# zx81a.net
KiCad netlist of a schematic drawn in EAGLE
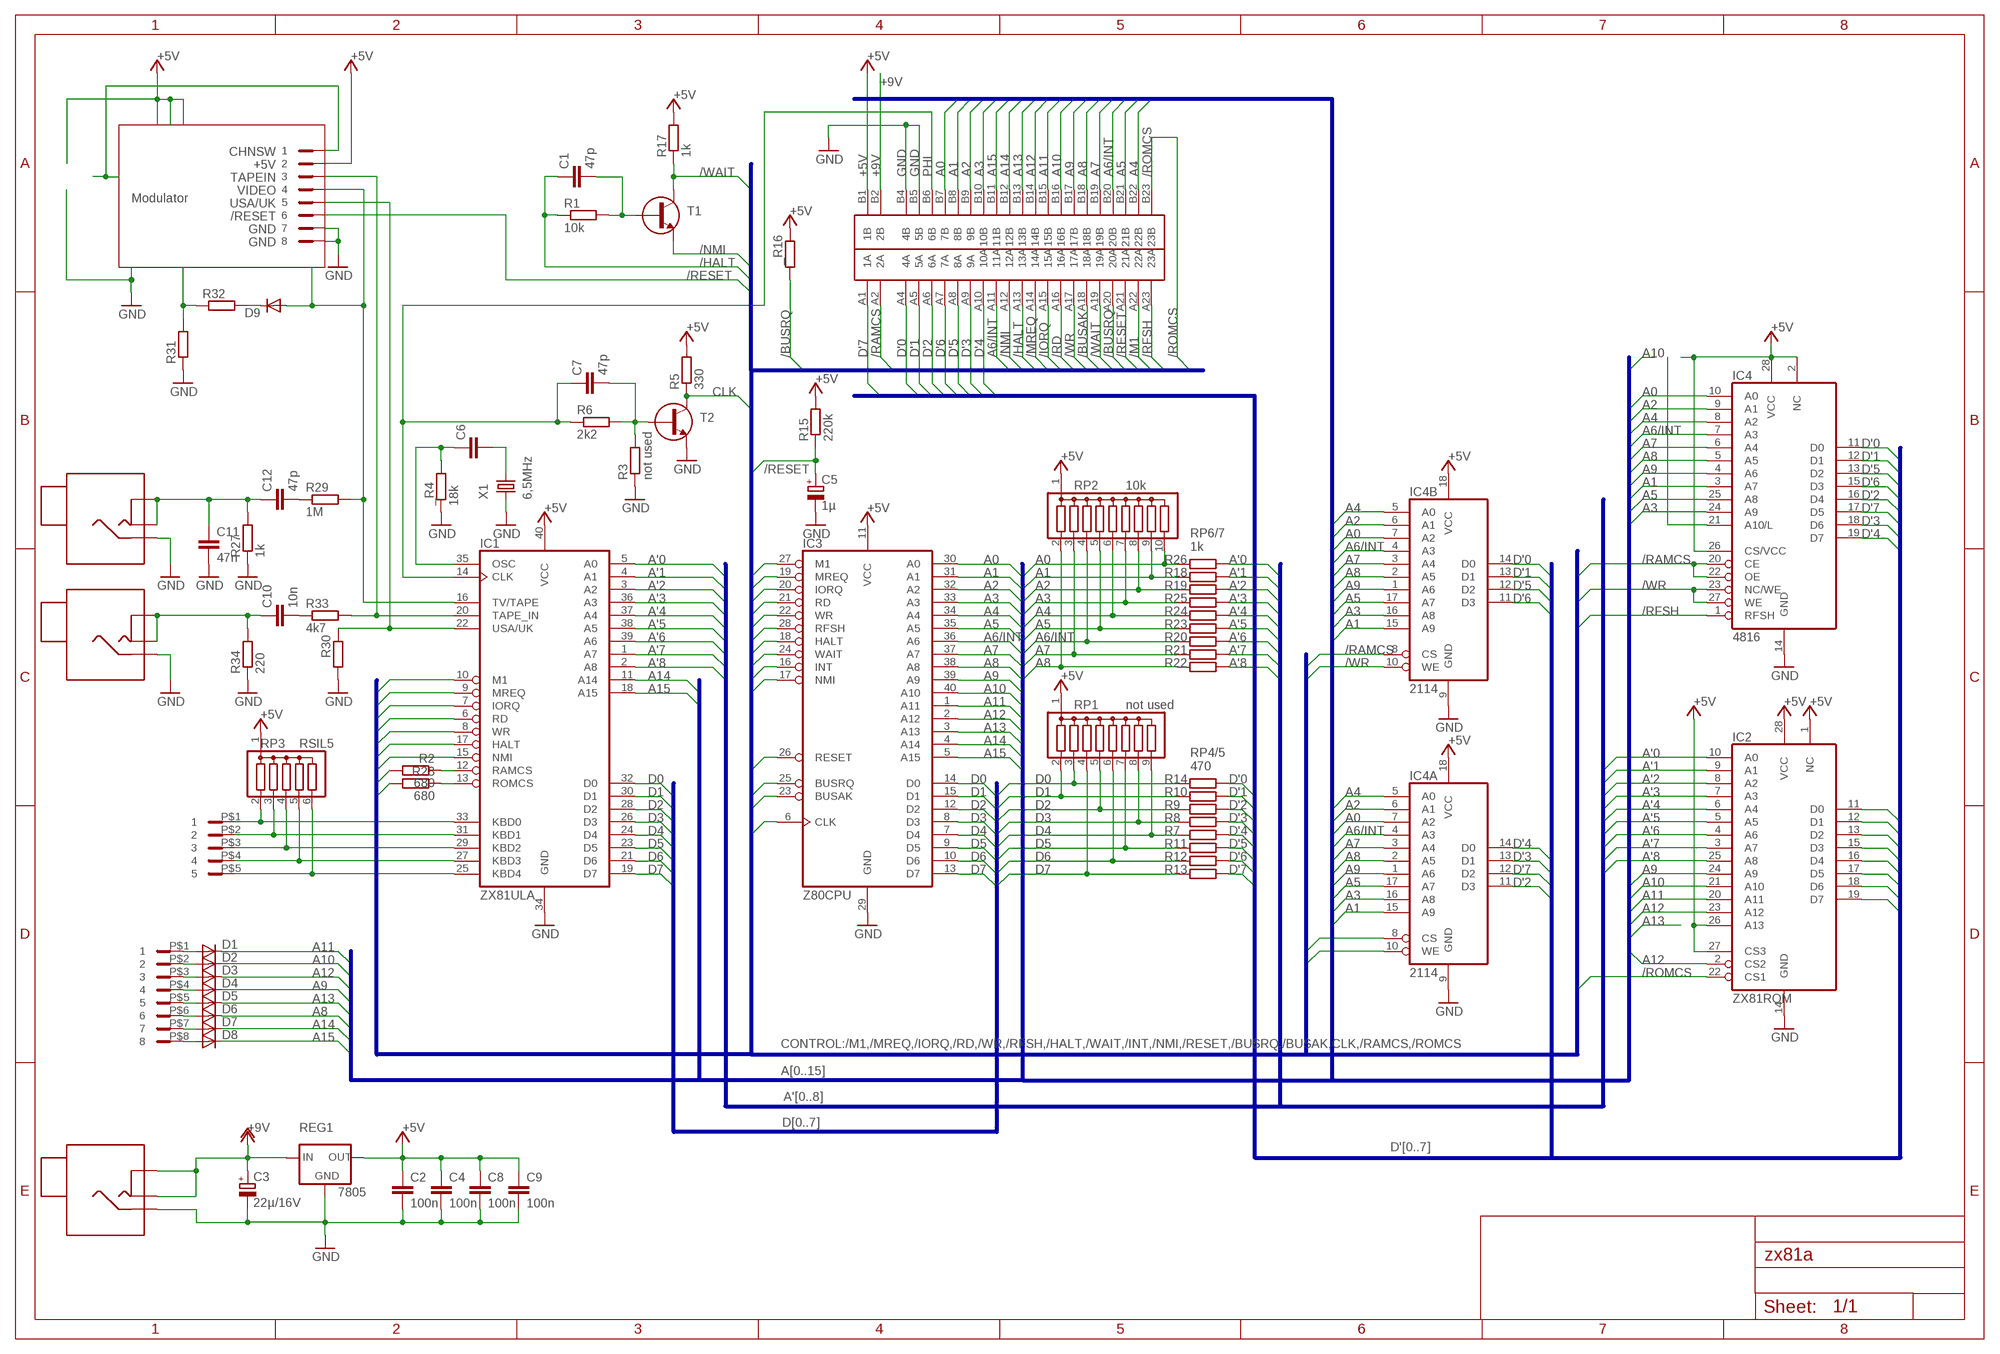
[diagram p0: schematic, sheet 1]

(export (version "E")
  (design (tool "Eeschema 10.0.6"))
  (components
    (comp (ref "C1")
      (value "47p")
      (footprint "eagle-import:C025-025X050")
      (libsource (lib "eagle-import") (part "C"))
    )
    (comp (ref "C2")
      (value "100n")
      (footprint "eagle-import:C025-025X050")
      (libsource (lib "eagle-import") (part "C"))
    )
    (comp (ref "C3")
      (value "22µ/16V")
      (footprint "eagle-import:E5-5")
      (libsource (lib "eagle-import") (part "CPOLE5-5"))
    )
    (comp (ref "C4")
      (value "100n")
      (footprint "eagle-import:C025-025X050")
      (libsource (lib "eagle-import") (part "C"))
    )
    (comp (ref "C5")
      (value "1µ")
      (footprint "eagle-import:E3,8-5")
      (libsource (lib "eagle-import") (part "CPOLE3,8-5"))
    )
    (comp (ref "C6")
      (value "C")
      (footprint "eagle-import:C025-025X050")
      (libsource (lib "eagle-import") (part "C"))
    )
    (comp (ref "C7")
      (value "47p")
      (footprint "eagle-import:C025-025X050")
      (libsource (lib "eagle-import") (part "C"))
    )
    (comp (ref "C8")
      (value "100n")
      (footprint "eagle-import:C025-025X050")
      (libsource (lib "eagle-import") (part "C"))
    )
    (comp (ref "C9")
      (value "100n")
      (footprint "eagle-import:C025-025X050")
      (libsource (lib "eagle-import") (part "C"))
    )
    (comp (ref "C10")
      (value "10n")
      (footprint "eagle-import:C025-025X050")
      (libsource (lib "eagle-import") (part "C"))
    )
    (comp (ref "C11")
      (value "47n")
      (footprint "eagle-import:C025-025X050")
      (libsource (lib "eagle-import") (part "C"))
    )
    (comp (ref "C12")
      (value "47p")
      (footprint "eagle-import:C025-025X050")
      (libsource (lib "eagle-import") (part "C"))
    )
    (comp (ref "D1")
      (value "DIODED10")
      (footprint "eagle-import:D10")
      (libsource (lib "eagle-import") (part "DIODED10"))
    )
    (comp (ref "D2")
      (value "DIODED10")
      (footprint "eagle-import:D10")
      (libsource (lib "eagle-import") (part "DIODED10"))
    )
    (comp (ref "D3")
      (value "DIODED10")
      (footprint "eagle-import:D10")
      (libsource (lib "eagle-import") (part "DIODED10"))
    )
    (comp (ref "D4")
      (value "DIODED10")
      (footprint "eagle-import:D10")
      (libsource (lib "eagle-import") (part "DIODED10"))
    )
    (comp (ref "D5")
      (value "DIODED10")
      (footprint "eagle-import:D10")
      (libsource (lib "eagle-import") (part "DIODED10"))
    )
    (comp (ref "D6")
      (value "DIODED10")
      (footprint "eagle-import:D10")
      (libsource (lib "eagle-import") (part "DIODED10"))
    )
    (comp (ref "D7")
      (value "DIODED10")
      (footprint "eagle-import:D10")
      (libsource (lib "eagle-import") (part "DIODED10"))
    )
    (comp (ref "D8")
      (value "DIODED10")
      (footprint "eagle-import:D10")
      (libsource (lib "eagle-import") (part "DIODED10"))
    )
    (comp (ref "D9")
      (value "DIODED15")
      (footprint "eagle-import:D15")
      (libsource (lib "eagle-import") (part "DIODED15"))
    )
    (comp (ref "IC1")
      (value "ZX81ULA")
      (footprint "eagle-import:DIL40")
      (libsource (lib "eagle-import") (part "ZX81ULA"))
    )
    (comp (ref "IC2")
      (value "ZX81ROM")
      (footprint "eagle-import:DIL24_28")
      (libsource (lib "eagle-import") (part "ZX81ROM"))
    )
    (comp (ref "IC3")
      (value "Z80CPU")
      (footprint "eagle-import:DIL40")
      (libsource (lib "eagle-import") (part "Z80CPU"))
    )
    (comp (ref "IC4")
      (value "4816")
      (footprint "eagle-import:DIL28")
      (libsource (lib "eagle-import") (part "4816"))
    )
    (comp (ref "IC4A")
      (value "2114")
      (footprint "eagle-import:DIL18")
      (libsource (lib "eagle-import") (part "2114"))
    )
    (comp (ref "IC4B")
      (value "2114")
      (footprint "eagle-import:DIL18")
      (libsource (lib "eagle-import") (part "2114"))
    )
    (comp (ref "K1")
      (value "ZX81CONN")
      (footprint "eagle-import:ZX81CON")
      (libsource (lib "eagle-import") (part "ZX81CONN"))
    )
    (comp (ref "K2")
      (value "MIC")
      (footprint "eagle-import:ZXKLINKE")
      (libsource (lib "eagle-import") (part "ZXKLINKE"))
    )
    (comp (ref "K3")
      (value "EAR")
      (footprint "eagle-import:ZXKLINKE")
      (libsource (lib "eagle-import") (part "ZXKLINKE"))
    )
    (comp (ref "K4")
      (value "DCIN")
      (footprint "eagle-import:ZXKLINKE")
      (libsource (lib "eagle-import") (part "ZXKLINKE"))
    )
    (comp (ref "K5")
      (value "PINHEAD-2X4")
      (footprint "eagle-import:PINHEAD2X4")
      (libsource (lib "eagle-import") (part "PINHEAD-2X4"))
    )
    (comp (ref "KB1")
      (value "ZXKBD5CON")
      (footprint "eagle-import:ZXKDB5")
      (libsource (lib "eagle-import") (part "ZXKBD5CON"))
    )
    (comp (ref "KB2")
      (value "ZXKBD8CON")
      (footprint "eagle-import:ZXKBD8")
      (libsource (lib "eagle-import") (part "ZXKBD8CON"))
    )
    (comp (ref "R1")
      (value "10k")
      (footprint "eagle-import:R207_12")
      (libsource (lib "eagle-import") (part "RR207/12"))
    )
    (comp (ref "R2")
      (value "680")
      (footprint "eagle-import:R207_12")
      (libsource (lib "eagle-import") (part "RR207/12"))
    )
    (comp (ref "R3")
      (value "not used")
      (footprint "eagle-import:R207_12")
      (libsource (lib "eagle-import") (part "RR207/12"))
    )
    (comp (ref "R5")
      (value "330")
      (footprint "eagle-import:R207_12")
      (libsource (lib "eagle-import") (part "RR207/12"))
    )
    (comp (ref "R6")
      (value "2k2")
      (footprint "eagle-import:R207_12")
      (libsource (lib "eagle-import") (part "RR207/12"))
    )
    (comp (ref "R15")
      (value "220k")
      (footprint "eagle-import:R207_12")
      (libsource (lib "eagle-import") (part "RR207/12"))
    )
    (comp (ref "R17")
      (value "1k")
      (footprint "eagle-import:R207_12")
      (libsource (lib "eagle-import") (part "RR207/12"))
    )
    (comp (ref "R27")
      (value "1k")
      (footprint "eagle-import:R207_12")
      (libsource (lib "eagle-import") (part "RR207/12"))
    )
    (comp (ref "R28")
      (value "680")
      (footprint "eagle-import:R207_12")
      (libsource (lib "eagle-import") (part "RR207/12"))
    )
    (comp (ref "R29")
      (value "1M")
      (footprint "eagle-import:R207_12")
      (libsource (lib "eagle-import") (part "RR207/12"))
    )
    (comp (ref "R30")
      (value "RR207/12")
      (footprint "eagle-import:R207_12")
      (libsource (lib "eagle-import") (part "RR207/12"))
    )
    (comp (ref "R31")
      (value "RR207/12")
      (footprint "eagle-import:R207_12")
      (libsource (lib "eagle-import") (part "RR207/12"))
    )
    (comp (ref "R32")
      (value "RR207/12")
      (footprint "eagle-import:R207_12")
      (libsource (lib "eagle-import") (part "RR207/12"))
    )
    (comp (ref "R33")
      (value "4k7")
      (footprint "eagle-import:R207_12")
      (libsource (lib "eagle-import") (part "RR207/12"))
    )
    (comp (ref "R34")
      (value "220")
      (footprint "eagle-import:R207_12")
      (libsource (lib "eagle-import") (part "RR207/12"))
    )
    (comp (ref "REG1")
      (value "7805")
      (footprint "eagle-import:78XXL")
      (libsource (lib "eagle-import") (part "78XX"))
    )
    (comp (ref "RP1")
      (value "not used")
      (footprint "eagle-import:SIL9")
      (libsource (lib "eagle-import") (part "RSIL8"))
    )
    (comp (ref "RP2")
      (value "10k")
      (footprint "eagle-import:SIL10")
      (libsource (lib "eagle-import") (part "RSIL9"))
    )
    (comp (ref "RP3")
      (value "RSIL5")
      (footprint "eagle-import:SIL6")
      (libsource (lib "eagle-import") (part "RSIL5"))
    )
    (comp (ref "RP4")
      (value "470")
      (footprint "eagle-import:SIL8P")
      (libsource (lib "eagle-import") (part "RSILP4"))
    )
    (comp (ref "RP5")
      (value "470")
      (footprint "eagle-import:SIL8P")
      (libsource (lib "eagle-import") (part "RSILP4"))
    )
    (comp (ref "RP6")
      (value "1k")
      (footprint "eagle-import:SIL8P")
      (libsource (lib "eagle-import") (part "RSILP4"))
    )
    (comp (ref "RP7")
      (value "RSILP5")
      (footprint "eagle-import:SIL10P")
      (libsource (lib "eagle-import") (part "RSILP5"))
    )
    (comp (ref "T1")
      (value "T-NPN-ZTX313TO92FLAT")
      (footprint "eagle-import:TO92FLAT")
      (libsource (lib "eagle-import") (part "T-NPN-ZTX313TO92FLAT"))
    )
    (comp (ref "T2")
      (value "T-NPN-ZTX313TO92FLAT")
      (footprint "eagle-import:TO92FLAT")
      (libsource (lib "eagle-import") (part "T-NPN-ZTX313TO92FLAT"))
    )
    (comp (ref "X1")
      (value "6,5MHz")
      (footprint "eagle-import:HC49")
      (libsource (lib "eagle-import") (part "CRYSTAL"))
    )
    (comp (ref "_R4")
      (value "18k")
      (footprint "eagle-import:R207_12")
      (libsource (lib "eagle-import") (part "RR207/12"))
    )
    (comp (ref "_R16")
      (value "RR207/12")
      (footprint "eagle-import:R207_12")
      (libsource (lib "eagle-import") (part "RR207/12"))
    )
  )
  (nets
    (net (code "4") (name "+5V") (class "Default")
      (node (ref "C2") (pin "1") (pinfunction "1_1") (pintype "passive"))
      (node (ref "C4") (pin "1") (pinfunction "1_1") (pintype "passive"))
      (node (ref "C8") (pin "1") (pinfunction "1_1") (pintype "passive"))
      (node (ref "C9") (pin "1") (pinfunction "1_1") (pintype "passive"))
      (node (ref "IC1") (pin "40") (pinfunction "VCC_40") (pintype "power_in"))
      (node (ref "IC2") (pin "1") (pinfunction "NC_1") (pintype "power_in"))
      (node (ref "IC2") (pin "26") (pinfunction "A13_26") (pintype "output"))
      (node (ref "IC2") (pin "27") (pinfunction "CS3_27") (pintype "output"))
      (node (ref "IC2") (pin "28") (pinfunction "VCC_28") (pintype "power_in"))
      (node (ref "IC3") (pin "11") (pinfunction "VCC_11") (pintype "power_in"))
      (node (ref "IC4") (pin "2") (pinfunction "NC_2") (pintype "power_in"))
      (node (ref "IC4") (pin "26") (pinfunction "CS/VCC_26") (pintype "output"))
      (node (ref "IC4") (pin "28") (pinfunction "VCC_28") (pintype "power_in"))
      (node (ref "IC4A") (pin "18") (pinfunction "VCC_18") (pintype "power_in"))
      (node (ref "IC4B") (pin "18") (pinfunction "VCC_18") (pintype "power_in"))
      (node (ref "K1") (pin "B1") (pinfunction "1B_B1") (pintype "bidirectional"))
      (node (ref "K5") (pin "2") (pinfunction "2_2") (pintype "bidirectional"))
      (node (ref "R15") (pin "2") (pinfunction "2_2") (pintype "passive"))
      (node (ref "R17") (pin "2") (pinfunction "2_2") (pintype "passive"))
      (node (ref "R5") (pin "2") (pinfunction "2_2") (pintype "passive"))
      (node (ref "REG1") (pin "OUT") (pinfunction "OUT_OUT") (pintype "passive"))
      (node (ref "RP1") (pin "1") (pinfunction "1_1") (pintype "passive"))
      (node (ref "RP2") (pin "1") (pinfunction "1_1") (pintype "passive"))
      (node (ref "RP3") (pin "1") (pinfunction "1_1") (pintype "passive"))
      (node (ref "_R16") (pin "1") (pinfunction "1_1") (pintype "passive"))
    )
    (net (code "5") (name "+9V") (class "Default")
      (node (ref "C3") (pin "+") (pinfunction "+_+") (pintype "passive"))
      (node (ref "K1") (pin "B2") (pinfunction "2B_B2") (pintype "bidirectional"))
      (node (ref "K4") (pin "1") (pinfunction "P$1_1") (pintype "bidirectional"))
      (node (ref "K4") (pin "1'") (pinfunction "P$1'_1'") (pintype "bidirectional"))
      (node (ref "REG1") (pin "IN") (pinfunction "IN_IN") (pintype "input"))
    )
    (net (code "6") (name "/A'0") (class "Default")
      (node (ref "IC1") (pin "5") (pinfunction "A0_5") (pintype "output"))
      (node (ref "IC2") (pin "10") (pinfunction "A0_10") (pintype "output"))
      (node (ref "RP6") (pin "7") (pinfunction "1_7") (pintype "passive"))
    )
    (net (code "7") (name "/A'1") (class "Default")
      (node (ref "IC1") (pin "4") (pinfunction "A1_4") (pintype "output"))
      (node (ref "IC2") (pin "9") (pinfunction "A1_9") (pintype "output"))
      (node (ref "RP7") (pin "2") (pinfunction "2_2") (pintype "passive"))
    )
    (net (code "8") (name "/A'2") (class "Default")
      (node (ref "IC1") (pin "3") (pinfunction "A2_3") (pintype "output"))
      (node (ref "IC2") (pin "8") (pinfunction "A2_8") (pintype "output"))
      (node (ref "RP7") (pin "3") (pinfunction "1_3") (pintype "passive"))
    )
    (net (code "9") (name "/A'3") (class "Default")
      (node (ref "IC1") (pin "36") (pinfunction "A3_36") (pintype "output"))
      (node (ref "IC2") (pin "7") (pinfunction "A3_7") (pintype "output"))
      (node (ref "RP6") (pin "5") (pinfunction "1_5") (pintype "passive"))
    )
    (net (code "10") (name "/A'4") (class "Default")
      (node (ref "IC1") (pin "37") (pinfunction "A4_37") (pintype "output"))
      (node (ref "IC2") (pin "6") (pinfunction "A4_6") (pintype "output"))
      (node (ref "RP6") (pin "3") (pinfunction "1_3") (pintype "passive"))
    )
    (net (code "11") (name "/A'5") (class "Default")
      (node (ref "IC1") (pin "38") (pinfunction "A5_38") (pintype "output"))
      (node (ref "IC2") (pin "5") (pinfunction "A5_5") (pintype "output"))
      (node (ref "RP6") (pin "1") (pinfunction "1_1") (pintype "passive"))
    )
    (net (code "12") (name "/A'6") (class "Default")
      (node (ref "IC1") (pin "39") (pinfunction "A6_39") (pintype "output"))
      (node (ref "IC2") (pin "4") (pinfunction "A6_4") (pintype "output"))
      (node (ref "RP7") (pin "5") (pinfunction "1_5") (pintype "passive"))
    )
    (net (code "13") (name "/A'7") (class "Default")
      (node (ref "IC1") (pin "1") (pinfunction "A7_1") (pintype "output"))
      (node (ref "IC2") (pin "3") (pinfunction "A7_3") (pintype "output"))
      (node (ref "RP7") (pin "7") (pinfunction "1_7") (pintype "passive"))
    )
    (net (code "14") (name "/A'8") (class "Default")
      (node (ref "IC1") (pin "2") (pinfunction "A8_2") (pintype "output"))
      (node (ref "IC2") (pin "25") (pinfunction "A8_25") (pintype "output"))
      (node (ref "RP7") (pin "9") (pinfunction "1_9") (pintype "passive"))
    )
    (net (code "16") (name "/A0") (class "Default")
      (node (ref "IC3") (pin "30") (pinfunction "A0_30") (pintype "output"))
      (node (ref "IC4") (pin "10") (pinfunction "A0_10") (pintype "output"))
      (node (ref "IC4A") (pin "7") (pinfunction "A2_7") (pintype "output"))
      (node (ref "IC4B") (pin "7") (pinfunction "A2_7") (pintype "output"))
      (node (ref "K1") (pin "B7") (pinfunction "7B_B7") (pintype "bidirectional"))
      (node (ref "RP2") (pin "10") (pinfunction "10_10") (pintype "passive"))
      (node (ref "RP6") (pin "8") (pinfunction "2_8") (pintype "passive"))
    )
    (net (code "17") (name "/A1") (class "Default")
      (node (ref "IC3") (pin "31") (pinfunction "A1_31") (pintype "output"))
      (node (ref "IC4") (pin "3") (pinfunction "A7_3") (pintype "output"))
      (node (ref "IC4A") (pin "15") (pinfunction "A9_15") (pintype "output"))
      (node (ref "IC4B") (pin "15") (pinfunction "A9_15") (pintype "output"))
      (node (ref "K1") (pin "B8") (pinfunction "8B_B8") (pintype "bidirectional"))
      (node (ref "RP2") (pin "9") (pinfunction "9_9") (pintype "passive"))
      (node (ref "RP7") (pin "1") (pinfunction "1_1") (pintype "passive"))
    )
    (net (code "18") (name "/A2") (class "Default")
      (node (ref "IC3") (pin "32") (pinfunction "A2_32") (pintype "output"))
      (node (ref "IC4") (pin "9") (pinfunction "A1_9") (pintype "output"))
      (node (ref "IC4A") (pin "6") (pinfunction "A1_6") (pintype "output"))
      (node (ref "IC4B") (pin "6") (pinfunction "A1_6") (pintype "output"))
      (node (ref "K1") (pin "B9") (pinfunction "9B_B9") (pintype "bidirectional"))
      (node (ref "RP2") (pin "8") (pinfunction "8_8") (pintype "passive"))
      (node (ref "RP7") (pin "4") (pinfunction "2_4") (pintype "passive"))
    )
    (net (code "19") (name "/A3") (class "Default")
      (node (ref "IC3") (pin "33") (pinfunction "A3_33") (pintype "output"))
      (node (ref "IC4") (pin "24") (pinfunction "A9_24") (pintype "output"))
      (node (ref "IC4A") (pin "16") (pinfunction "A8_16") (pintype "output"))
      (node (ref "IC4B") (pin "16") (pinfunction "A8_16") (pintype "output"))
      (node (ref "K1") (pin "B10") (pinfunction "10B_B10") (pintype "bidirectional"))
      (node (ref "RP2") (pin "7") (pinfunction "7_7") (pintype "passive"))
      (node (ref "RP6") (pin "6") (pinfunction "2_6") (pintype "passive"))
    )
    (net (code "20") (name "/A4") (class "Default")
      (node (ref "IC3") (pin "34") (pinfunction "A4_34") (pintype "output"))
      (node (ref "IC4") (pin "8") (pinfunction "A2_8") (pintype "output"))
      (node (ref "IC4A") (pin "5") (pinfunction "A0_5") (pintype "output"))
      (node (ref "IC4B") (pin "5") (pinfunction "A0_5") (pintype "output"))
      (node (ref "K1") (pin "B22") (pinfunction "22B_B22") (pintype "bidirectional"))
      (node (ref "RP2") (pin "6") (pinfunction "6_6") (pintype "passive"))
      (node (ref "RP6") (pin "4") (pinfunction "2_4") (pintype "passive"))
    )
    (net (code "21") (name "/A5") (class "Default")
      (node (ref "IC3") (pin "35") (pinfunction "A5_35") (pintype "output"))
      (node (ref "IC4") (pin "25") (pinfunction "A8_25") (pintype "output"))
      (node (ref "IC4A") (pin "17") (pinfunction "A7_17") (pintype "output"))
      (node (ref "IC4B") (pin "17") (pinfunction "A7_17") (pintype "output"))
      (node (ref "K1") (pin "B21") (pinfunction "21B_B21") (pintype "bidirectional"))
      (node (ref "RP2") (pin "5") (pinfunction "5_5") (pintype "passive"))
      (node (ref "RP6") (pin "2") (pinfunction "2_2") (pintype "passive"))
    )
    (net (code "22") (name "/A6{slash}INT") (class "Default")
      (node (ref "IC3") (pin "16") (pinfunction "INT_16") (pintype "input"))
      (node (ref "IC3") (pin "36") (pinfunction "A6_36") (pintype "output"))
      (node (ref "IC4") (pin "7") (pinfunction "A3_7") (pintype "output"))
      (node (ref "IC4A") (pin "4") (pinfunction "A3_4") (pintype "output"))
      (node (ref "IC4B") (pin "4") (pinfunction "A3_4") (pintype "output"))
      (node (ref "K1") (pin "A11") (pinfunction "11A_A11") (pintype "bidirectional"))
      (node (ref "K1") (pin "B20") (pinfunction "20B_B20") (pintype "bidirectional"))
      (node (ref "RP2") (pin "4") (pinfunction "4_4") (pintype "passive"))
      (node (ref "RP7") (pin "6") (pinfunction "2_6") (pintype "passive"))
    )
    (net (code "23") (name "/A7") (class "Default")
      (node (ref "IC3") (pin "37") (pinfunction "A7_37") (pintype "output"))
      (node (ref "IC4") (pin "6") (pinfunction "A4_6") (pintype "output"))
      (node (ref "IC4A") (pin "3") (pinfunction "A4_3") (pintype "output"))
      (node (ref "IC4B") (pin "3") (pinfunction "A4_3") (pintype "output"))
      (node (ref "K1") (pin "B19") (pinfunction "19B_B19") (pintype "bidirectional"))
      (node (ref "RP2") (pin "3") (pinfunction "3_3") (pintype "passive"))
      (node (ref "RP7") (pin "8") (pinfunction "2_8") (pintype "passive"))
    )
    (net (code "24") (name "/A8") (class "Default")
      (node (ref "D6") (pin "C") (pinfunction "C_C") (pintype "passive"))
      (node (ref "IC3") (pin "38") (pinfunction "A8_38") (pintype "output"))
      (node (ref "IC4") (pin "5") (pinfunction "A5_5") (pintype "output"))
      (node (ref "IC4A") (pin "2") (pinfunction "A5_2") (pintype "output"))
      (node (ref "IC4B") (pin "2") (pinfunction "A5_2") (pintype "output"))
      (node (ref "K1") (pin "B18") (pinfunction "18B_B18") (pintype "bidirectional"))
      (node (ref "RP2") (pin "2") (pinfunction "2_2") (pintype "passive"))
      (node (ref "RP7") (pin "10") (pinfunction "2_10") (pintype "passive"))
    )
    (net (code "25") (name "/A9") (class "Default")
      (node (ref "D4") (pin "C") (pinfunction "C_C") (pintype "passive"))
      (node (ref "IC2") (pin "24") (pinfunction "A9_24") (pintype "output"))
      (node (ref "IC3") (pin "39") (pinfunction "A9_39") (pintype "output"))
      (node (ref "IC4") (pin "4") (pinfunction "A6_4") (pintype "output"))
      (node (ref "IC4A") (pin "1") (pinfunction "A6_1") (pintype "output"))
      (node (ref "IC4B") (pin "1") (pinfunction "A6_1") (pintype "output"))
      (node (ref "K1") (pin "B17") (pinfunction "17B_B17") (pintype "bidirectional"))
    )
    (net (code "26") (name "/A10") (class "Default")
      (node (ref "D2") (pin "C") (pinfunction "C_C") (pintype "passive"))
      (node (ref "IC2") (pin "21") (pinfunction "A10_21") (pintype "output"))
      (node (ref "IC3") (pin "40") (pinfunction "A10_40") (pintype "output"))
      (node (ref "K1") (pin "B16") (pinfunction "16B_B16") (pintype "bidirectional"))
    )
    (net (code "27") (name "/A11") (class "Default")
      (node (ref "D1") (pin "C") (pinfunction "C_C") (pintype "passive"))
      (node (ref "IC2") (pin "20") (pinfunction "A11_20") (pintype "output"))
      (node (ref "IC3") (pin "1") (pinfunction "A11_1") (pintype "output"))
      (node (ref "K1") (pin "B15") (pinfunction "15B_B15") (pintype "bidirectional"))
    )
    (net (code "28") (name "/A12") (class "Default")
      (node (ref "D3") (pin "C") (pinfunction "C_C") (pintype "passive"))
      (node (ref "IC2") (pin "2") (pinfunction "CS2_2") (pintype "output"))
      (node (ref "IC2") (pin "23") (pinfunction "A12_23") (pintype "output"))
      (node (ref "IC3") (pin "2") (pinfunction "A12_2") (pintype "output"))
      (node (ref "K1") (pin "B14") (pinfunction "14B_B14") (pintype "bidirectional"))
    )
    (net (code "29") (name "/A13") (class "Default")
      (node (ref "D5") (pin "C") (pinfunction "C_C") (pintype "passive"))
      (node (ref "IC3") (pin "3") (pinfunction "A13_3") (pintype "output"))
      (node (ref "K1") (pin "B13") (pinfunction "13B_B13") (pintype "bidirectional"))
    )
    (net (code "30") (name "/A14") (class "Default")
      (node (ref "D7") (pin "C") (pinfunction "C_C") (pintype "passive"))
      (node (ref "IC1") (pin "11") (pinfunction "A14_11") (pintype "output"))
      (node (ref "IC3") (pin "4") (pinfunction "A14_4") (pintype "output"))
      (node (ref "K1") (pin "B12") (pinfunction "12B_B12") (pintype "bidirectional"))
    )
    (net (code "31") (name "/A15") (class "Default")
      (node (ref "D8") (pin "C") (pinfunction "C_C") (pintype "passive"))
      (node (ref "IC1") (pin "18") (pinfunction "A15_18") (pintype "output"))
      (node (ref "IC3") (pin "5") (pinfunction "A15_5") (pintype "output"))
      (node (ref "K1") (pin "B11") (pinfunction "11B_B11") (pintype "bidirectional"))
    )
    (net (code "33") (name "/CHNSW") (class "Default")
      (node (ref "K5") (pin "1") (pinfunction "1_1") (pintype "bidirectional"))
    )
    (net (code "34") (name "/CLK") (class "Default")
      (node (ref "IC3") (pin "6") (pinfunction "CLK_6") (pintype "input"))
      (node (ref "R5") (pin "1") (pinfunction "1_1") (pintype "passive"))
      (node (ref "T2") (pin "2") (pinfunction "C_2") (pintype "passive"))
    )
    (net (code "35") (name "/D'0") (class "Default")
      (node (ref "IC2") (pin "11") (pinfunction "D0_11") (pintype "bidirectional"))
      (node (ref "IC4") (pin "11") (pinfunction "D0_11") (pintype "bidirectional"))
      (node (ref "IC4B") (pin "14") (pinfunction "D0_14") (pintype "bidirectional"))
      (node (ref "K1") (pin "A4") (pinfunction "4A_A4") (pintype "bidirectional"))
      (node (ref "RP5") (pin "8") (pinfunction "2_8") (pintype "passive"))
    )
    (net (code "36") (name "/D'1") (class "Default")
      (node (ref "IC2") (pin "12") (pinfunction "D1_12") (pintype "bidirectional"))
      (node (ref "IC4") (pin "12") (pinfunction "D1_12") (pintype "bidirectional"))
      (node (ref "IC4B") (pin "13") (pinfunction "D1_13") (pintype "bidirectional"))
      (node (ref "K1") (pin "A5") (pinfunction "5A_A5") (pintype "bidirectional"))
      (node (ref "RP4") (pin "8") (pinfunction "2_8") (pintype "passive"))
    )
    (net (code "37") (name "/D'2") (class "Default")
      (node (ref "IC2") (pin "13") (pinfunction "D2_13") (pintype "bidirectional"))
      (node (ref "IC4") (pin "16") (pinfunction "D4_16") (pintype "bidirectional"))
      (node (ref "IC4A") (pin "11") (pinfunction "D3_11") (pintype "bidirectional"))
      (node (ref "K1") (pin "A6") (pinfunction "6A_A6") (pintype "bidirectional"))
      (node (ref "RP4") (pin "6") (pinfunction "2_6") (pintype "passive"))
    )
    (net (code "38") (name "/D'3") (class "Default")
      (node (ref "IC2") (pin "15") (pinfunction "D3_15") (pintype "bidirectional"))
      (node (ref "IC4") (pin "18") (pinfunction "D6_18") (pintype "bidirectional"))
      (node (ref "IC4A") (pin "13") (pinfunction "D1_13") (pintype "bidirectional"))
      (node (ref "K1") (pin "A9") (pinfunction "9A_A9") (pintype "bidirectional"))
      (node (ref "RP4") (pin "4") (pinfunction "2_4") (pintype "passive"))
    )
    (net (code "39") (name "/D'4") (class "Default")
      (node (ref "IC2") (pin "16") (pinfunction "D4_16") (pintype "bidirectional"))
      (node (ref "IC4") (pin "19") (pinfunction "D7_19") (pintype "bidirectional"))
      (node (ref "IC4A") (pin "14") (pinfunction "D0_14") (pintype "bidirectional"))
      (node (ref "K1") (pin "A10") (pinfunction "10A_A10") (pintype "bidirectional"))
      (node (ref "RP4") (pin "1") (pinfunction "1_1") (pintype "passive"))
    )
    (net (code "40") (name "/D'5") (class "Default")
      (node (ref "IC2") (pin "17") (pinfunction "D5_17") (pintype "bidirectional"))
      (node (ref "IC4") (pin "13") (pinfunction "D2_13") (pintype "bidirectional"))
      (node (ref "IC4B") (pin "12") (pinfunction "D2_12") (pintype "bidirectional"))
      (node (ref "K1") (pin "A8") (pinfunction "8A_A8") (pintype "bidirectional"))
      (node (ref "RP5") (pin "1") (pinfunction "1_1") (pintype "passive"))
    )
    (net (code "41") (name "/D'6") (class "Default")
      (node (ref "IC2") (pin "18") (pinfunction "D6_18") (pintype "bidirectional"))
      (node (ref "IC4") (pin "15") (pinfunction "D3_15") (pintype "bidirectional"))
      (node (ref "IC4B") (pin "11") (pinfunction "D3_11") (pintype "bidirectional"))
      (node (ref "K1") (pin "A7") (pinfunction "7A_A7") (pintype "bidirectional"))
      (node (ref "RP5") (pin "4") (pinfunction "2_4") (pintype "passive"))
    )
    (net (code "42") (name "/D'7") (class "Default")
      (node (ref "IC2") (pin "19") (pinfunction "D7_19") (pintype "bidirectional"))
      (node (ref "IC4") (pin "17") (pinfunction "D5_17") (pintype "bidirectional"))
      (node (ref "IC4A") (pin "12") (pinfunction "D2_12") (pintype "bidirectional"))
      (node (ref "K1") (pin "A1") (pinfunction "1A_A1") (pintype "bidirectional"))
      (node (ref "RP5") (pin "5") (pinfunction "1_5") (pintype "passive"))
    )
    (net (code "44") (name "/D0") (class "Default")
      (node (ref "IC1") (pin "32") (pinfunction "D0_32") (pintype "bidirectional"))
      (node (ref "IC3") (pin "14") (pinfunction "D0_14") (pintype "bidirectional"))
      (node (ref "RP1") (pin "3") (pinfunction "3_3") (pintype "passive"))
      (node (ref "RP5") (pin "7") (pinfunction "1_7") (pintype "passive"))
    )
    (net (code "45") (name "/D1") (class "Default")
      (node (ref "IC1") (pin "30") (pinfunction "D1_30") (pintype "bidirectional"))
      (node (ref "IC3") (pin "15") (pinfunction "D1_15") (pintype "bidirectional"))
      (node (ref "RP1") (pin "2") (pinfunction "2_2") (pintype "passive"))
      (node (ref "RP4") (pin "7") (pinfunction "1_7") (pintype "passive"))
    )
    (net (code "46") (name "/D2") (class "Default")
      (node (ref "IC1") (pin "28") (pinfunction "D2_28") (pintype "bidirectional"))
      (node (ref "IC3") (pin "12") (pinfunction "D2_12") (pintype "bidirectional"))
      (node (ref "RP1") (pin "5") (pinfunction "5_5") (pintype "passive"))
      (node (ref "RP4") (pin "5") (pinfunction "1_5") (pintype "passive"))
    )
    (net (code "47") (name "/D3") (class "Default")
      (node (ref "IC1") (pin "26") (pinfunction "D3_26") (pintype "bidirectional"))
      (node (ref "IC3") (pin "8") (pinfunction "D3_8") (pintype "bidirectional"))
      (node (ref "RP1") (pin "8") (pinfunction "8_8") (pintype "passive"))
      (node (ref "RP4") (pin "3") (pinfunction "1_3") (pintype "passive"))
    )
    (net (code "48") (name "/D4") (class "Default")
      (node (ref "IC1") (pin "24") (pinfunction "D4_24") (pintype "bidirectional"))
      (node (ref "IC3") (pin "7") (pinfunction "D4_7") (pintype "bidirectional"))
      (node (ref "RP1") (pin "9") (pinfunction "9_9") (pintype "passive"))
      (node (ref "RP4") (pin "2") (pinfunction "2_2") (pintype "passive"))
    )
    (net (code "49") (name "/D5") (class "Default")
      (node (ref "IC1") (pin "23") (pinfunction "D5_23") (pintype "bidirectional"))
      (node (ref "IC3") (pin "9") (pinfunction "D5_9") (pintype "bidirectional"))
      (node (ref "RP1") (pin "7") (pinfunction "7_7") (pintype "passive"))
      (node (ref "RP5") (pin "2") (pinfunction "2_2") (pintype "passive"))
    )
    (net (code "50") (name "/D6") (class "Default")
      (node (ref "IC1") (pin "21") (pinfunction "D6_21") (pintype "bidirectional"))
      (node (ref "IC3") (pin "10") (pinfunction "D6_10") (pintype "bidirectional"))
      (node (ref "RP1") (pin "6") (pinfunction "6_6") (pintype "passive"))
      (node (ref "RP5") (pin "3") (pinfunction "1_3") (pintype "passive"))
    )
    (net (code "51") (name "/D7") (class "Default")
      (node (ref "IC1") (pin "19") (pinfunction "D7_19") (pintype "bidirectional"))
      (node (ref "IC3") (pin "13") (pinfunction "D7_13") (pintype "bidirectional"))
      (node (ref "RP1") (pin "4") (pinfunction "4_4") (pintype "passive"))
      (node (ref "RP5") (pin "6") (pinfunction "2_6") (pintype "passive"))
    )
    (net (code "53") (name "/PHI") (class "Default")
      (node (ref "C7") (pin "1") (pinfunction "1_1") (pintype "passive"))
      (node (ref "IC1") (pin "14") (pinfunction "CLK_14") (pintype "input"))
      (node (ref "K1") (pin "B6") (pinfunction "6B_B6") (pintype "bidirectional"))
      (node (ref "R6") (pin "1") (pinfunction "1_1") (pintype "passive"))
    )
    (net (code "54") (name "/TAPEIN") (class "Default")
      (node (ref "IC1") (pin "20") (pinfunction "TAPE_IN_20") (pintype "output"))
      (node (ref "K5") (pin "3") (pinfunction "3_3") (pintype "bidirectional"))
      (node (ref "R33") (pin "2") (pinfunction "2_2") (pintype "passive"))
    )
    (net (code "55") (name "/USA{slash}UK") (class "Default")
      (node (ref "IC1") (pin "22") (pinfunction "USA/UK_22") (pintype "output"))
      (node (ref "K5") (pin "5") (pinfunction "5_5") (pintype "bidirectional"))
      (node (ref "R30") (pin "1") (pinfunction "1_1") (pintype "passive"))
    )
    (net (code "56") (name "/VIDEO") (class "Default")
      (node (ref "D9") (pin "A") (pinfunction "A_A") (pintype "passive"))
      (node (ref "IC1") (pin "16") (pinfunction "TV/TAPE_16") (pintype "output"))
      (node (ref "K5") (pin "4") (pinfunction "4_4") (pintype "bidirectional"))
      (node (ref "R29") (pin "2") (pinfunction "2_2") (pintype "passive"))
    )
    (net (code "58") (name "/{slash}BUSAK") (class "Default")
      (node (ref "IC3") (pin "23") (pinfunction "BUSAK_23") (pintype "output"))
      (node (ref "K1") (pin "A18") (pinfunction "18A_A18") (pintype "bidirectional"))
    )
    (net (code "59") (name "/{slash}BUSRQ") (class "Default")
      (node (ref "IC3") (pin "25") (pinfunction "BUSRQ_25") (pintype "input"))
      (node (ref "K1") (pin "A20") (pinfunction "20A_A20") (pintype "bidirectional"))
      (node (ref "_R16") (pin "2") (pinfunction "2_2") (pintype "passive"))
    )
    (net (code "60") (name "/{slash}HALT") (class "Default")
      (node (ref "C1") (pin "1") (pinfunction "1_1") (pintype "passive"))
      (node (ref "IC1") (pin "17") (pinfunction "HALT_17") (pintype "output"))
      (node (ref "IC3") (pin "18") (pinfunction "HALT_18") (pintype "output"))
      (node (ref "K1") (pin "A13") (pinfunction "13A_A13") (pintype "bidirectional"))
      (node (ref "R1") (pin "1") (pinfunction "1_1") (pintype "passive"))
    )
    (net (code "61") (name "/{slash}IORQ") (class "Default")
      (node (ref "IC1") (pin "7") (pinfunction "IORQ_7") (pintype "output"))
      (node (ref "IC3") (pin "20") (pinfunction "IORQ_20") (pintype "output"))
      (node (ref "K1") (pin "A15") (pinfunction "15A_A15") (pintype "bidirectional"))
    )
    (net (code "62") (name "/{slash}M1") (class "Default")
      (node (ref "IC1") (pin "10") (pinfunction "M1_10") (pintype "output"))
      (node (ref "IC3") (pin "27") (pinfunction "M1_27") (pintype "output"))
      (node (ref "K1") (pin "A22") (pinfunction "22A_A22") (pintype "bidirectional"))
    )
    (net (code "63") (name "/{slash}MREQ") (class "Default")
      (node (ref "IC1") (pin "9") (pinfunction "MREQ_9") (pintype "output"))
      (node (ref "IC3") (pin "19") (pinfunction "MREQ_19") (pintype "output"))
      (node (ref "K1") (pin "A14") (pinfunction "14A_A14") (pintype "bidirectional"))
    )
    (net (code "64") (name "/{slash}NMI") (class "Default")
      (node (ref "IC1") (pin "15") (pinfunction "NMI_15") (pintype "input"))
      (node (ref "IC3") (pin "17") (pinfunction "NMI_17") (pintype "input"))
      (node (ref "K1") (pin "A12") (pinfunction "12A_A12") (pintype "bidirectional"))
      (node (ref "T1") (pin "3") (pinfunction "E_3") (pintype "passive"))
    )
    (net (code "65") (name "/{slash}RAMCS") (class "Default")
      (node (ref "IC4") (pin "20") (pinfunction "CE_20") (pintype "output"))
      (node (ref "IC4") (pin "22") (pinfunction "OE_22") (pintype "output"))
      (node (ref "IC4A") (pin "8") (pinfunction "CS_8") (pintype "output"))
      (node (ref "IC4B") (pin "8") (pinfunction "CS_8") (pintype "output"))
      (node (ref "K1") (pin "A2") (pinfunction "2A_A2") (pintype "bidirectional"))
      (node (ref "R2") (pin "2") (pinfunction "2_2") (pintype "passive"))
    )
    (net (code "66") (name "/{slash}RD") (class "Default")
      (node (ref "IC1") (pin "6") (pinfunction "RD_6") (pintype "output"))
      (node (ref "IC3") (pin "21") (pinfunction "RD_21") (pintype "output"))
      (node (ref "K1") (pin "A16") (pinfunction "16A_A16") (pintype "bidirectional"))
    )
    (net (code "67") (name "/{slash}RESET") (class "Default")
      (node (ref "C5") (pin "+") (pinfunction "+_+") (pintype "passive"))
      (node (ref "IC3") (pin "26") (pinfunction "RESET_26") (pintype "input"))
      (node (ref "K1") (pin "A21") (pinfunction "21A_A21") (pintype "bidirectional"))
      (node (ref "K5") (pin "6") (pinfunction "6_6") (pintype "bidirectional"))
      (node (ref "R15") (pin "1") (pinfunction "1_1") (pintype "passive"))
    )
    (net (code "68") (name "/{slash}RFSH") (class "Default")
      (node (ref "IC3") (pin "28") (pinfunction "RFSH_28") (pintype "output"))
      (node (ref "IC4") (pin "1") (pinfunction "RFSH_1") (pintype "output"))
      (node (ref "K1") (pin "A23") (pinfunction "23A_A23") (pintype "bidirectional"))
    )
    (net (code "69") (name "/{slash}ROMCS") (class "Default")
      (node (ref "IC2") (pin "22") (pinfunction "CS1_22") (pintype "output"))
      (node (ref "K1") (pin "B23") (pinfunction "23B_B23") (pintype "bidirectional"))
      (node (ref "R28") (pin "2") (pinfunction "2_2") (pintype "passive"))
    )
    (net (code "70") (name "/{slash}WAIT") (class "Default")
      (node (ref "IC3") (pin "24") (pinfunction "WAIT_24") (pintype "input"))
      (node (ref "K1") (pin "A19") (pinfunction "19A_A19") (pintype "bidirectional"))
      (node (ref "R17") (pin "1") (pinfunction "1_1") (pintype "passive"))
      (node (ref "T1") (pin "2") (pinfunction "C_2") (pintype "passive"))
    )
    (net (code "71") (name "/{slash}WR") (class "Default")
      (node (ref "IC1") (pin "8") (pinfunction "WR_8") (pintype "output"))
      (node (ref "IC3") (pin "22") (pinfunction "WR_22") (pintype "output"))
      (node (ref "IC4") (pin "23") (pinfunction "NC/WE_23") (pintype "output"))
      (node (ref "IC4") (pin "27") (pinfunction "WE_27") (pintype "output"))
      (node (ref "IC4A") (pin "10") (pinfunction "WE_10") (pintype "output"))
      (node (ref "IC4B") (pin "10") (pinfunction "WE_10") (pintype "output"))
      (node (ref "K1") (pin "A17") (pinfunction "17A_A17") (pintype "bidirectional"))
    )
    (net (code "72") (name "GND") (class "Default")
      (node (ref "C11") (pin "2") (pinfunction "2_2") (pintype "passive"))
      (node (ref "C2") (pin "2") (pinfunction "2_2") (pintype "passive"))
      (node (ref "C3") (pin "-") (pinfunction "-_-") (pintype "passive"))
      (node (ref "C4") (pin "2") (pinfunction "2_2") (pintype "passive"))
      (node (ref "C5") (pin "-") (pinfunction "-_-") (pintype "passive"))
      (node (ref "C8") (pin "2") (pinfunction "2_2") (pintype "passive"))
      (node (ref "C9") (pin "2") (pinfunction "2_2") (pintype "passive"))
      (node (ref "IC1") (pin "34") (pinfunction "GND_34") (pintype "power_in"))
      (node (ref "IC2") (pin "14") (pinfunction "GND_14") (pintype "power_in"))
      (node (ref "IC3") (pin "29") (pinfunction "GND_29") (pintype "power_in"))
      (node (ref "IC4") (pin "14") (pinfunction "GND_14") (pintype "power_in"))
      (node (ref "IC4A") (pin "9") (pinfunction "GND_9") (pintype "power_in"))
      (node (ref "IC4B") (pin "9") (pinfunction "GND_9") (pintype "power_in"))
      (node (ref "K1") (pin "B4") (pinfunction "4B_B4") (pintype "bidirectional"))
      (node (ref "K1") (pin "B5") (pinfunction "5B_B5") (pintype "bidirectional"))
      (node (ref "K2") (pin "2") (pinfunction "P$2_2") (pintype "bidirectional"))
      (node (ref "K3") (pin "2") (pinfunction "P$2_2") (pintype "bidirectional"))
      (node (ref "K4") (pin "2") (pinfunction "P$2_2") (pintype "bidirectional"))
      (node (ref "K5") (pin "7") (pinfunction "7_7") (pintype "bidirectional"))
      (node (ref "K5") (pin "8") (pinfunction "8_8") (pintype "bidirectional"))
      (node (ref "R27") (pin "1") (pinfunction "1_1") (pintype "passive"))
      (node (ref "R3") (pin "1") (pinfunction "1_1") (pintype "passive"))
      (node (ref "R30") (pin "2") (pinfunction "2_2") (pintype "passive"))
      (node (ref "R31") (pin "1") (pinfunction "1_1") (pintype "passive"))
      (node (ref "R34") (pin "1") (pinfunction "1_1") (pintype "passive"))
      (node (ref "REG1") (pin "GND") (pinfunction "GND_GND") (pintype "input"))
      (node (ref "T2") (pin "3") (pinfunction "E_3") (pintype "passive"))
      (node (ref "X1") (pin "1") (pinfunction "1_1") (pintype "passive"))
      (node (ref "_R4") (pin "1") (pinfunction "1_1") (pintype "passive"))
    )
    (net (code "73") (name "Net-(C6-Pad2)") (class "Default")
      (node (ref "C6") (pin "2") (pinfunction "2_2") (pintype "passive"))
      (node (ref "X1") (pin "2") (pinfunction "2_2") (pintype "passive"))
    )
    (net (code "74") (name "Net-(C10-Pad2)") (class "Default")
      (node (ref "C10") (pin "2") (pinfunction "2_2") (pintype "passive"))
      (node (ref "R33") (pin "1") (pinfunction "1_1") (pintype "passive"))
    )
    (net (code "75") (name "Net-(C12-Pad2)") (class "Default")
      (node (ref "C12") (pin "2") (pinfunction "2_2") (pintype "passive"))
      (node (ref "R29") (pin "1") (pinfunction "1_1") (pintype "passive"))
    )
    (net (code "76") (name "Net-(D9-PadC)") (class "Default")
      (node (ref "D9") (pin "C") (pinfunction "C_C") (pintype "passive"))
      (node (ref "R32") (pin "2") (pinfunction "2_2") (pintype "passive"))
    )
    (net (code "77") (name "Net-(IC1-KBD0)") (class "Default")
      (node (ref "IC1") (pin "33") (pinfunction "KBD0_33") (pintype "output"))
      (node (ref "KB1") (pin "P$1") (pinfunction "1_P$1") (pintype "bidirectional"))
      (node (ref "RP3") (pin "2") (pinfunction "2_2") (pintype "passive"))
    )
    (net (code "78") (name "Net-(IC1-KBD1)") (class "Default")
      (node (ref "IC1") (pin "31") (pinfunction "KBD1_31") (pintype "input"))
      (node (ref "KB1") (pin "P$2") (pinfunction "2_P$2") (pintype "bidirectional"))
      (node (ref "RP3") (pin "3") (pinfunction "3_3") (pintype "passive"))
    )
    (net (code "79") (name "Net-(IC1-KBD2)") (class "Default")
      (node (ref "IC1") (pin "29") (pinfunction "KBD2_29") (pintype "input"))
      (node (ref "KB1") (pin "P$3") (pinfunction "3_P$3") (pintype "bidirectional"))
      (node (ref "RP3") (pin "4") (pinfunction "4_4") (pintype "passive"))
    )
    (net (code "80") (name "Net-(IC1-KBD3)") (class "Default")
      (node (ref "IC1") (pin "27") (pinfunction "KBD3_27") (pintype "input"))
      (node (ref "KB1") (pin "P$4") (pinfunction "4_P$4") (pintype "bidirectional"))
      (node (ref "RP3") (pin "5") (pinfunction "5_5") (pintype "passive"))
    )
    (net (code "81") (name "Net-(IC1-KBD4)") (class "Default")
      (node (ref "IC1") (pin "25") (pinfunction "KBD4_25") (pintype "input"))
      (node (ref "KB1") (pin "P$5") (pinfunction "5_P$5") (pintype "bidirectional"))
      (node (ref "RP3") (pin "6") (pinfunction "6_6") (pintype "passive"))
    )
    (net (code "82") (name "Net-(IC1-OSC)") (class "Default")
      (node (ref "C6") (pin "1") (pinfunction "1_1") (pintype "passive"))
      (node (ref "IC1") (pin "35") (pinfunction "OSC_35") (pintype "output"))
      (node (ref "_R4") (pin "2") (pinfunction "2_2") (pintype "passive"))
    )
    (net (code "83") (name "Net-(IC1-RAMCS)") (class "Default")
      (node (ref "IC1") (pin "12") (pinfunction "RAMCS_12") (pintype "output"))
      (node (ref "R2") (pin "1") (pinfunction "1_1") (pintype "passive"))
    )
    (net (code "84") (name "Net-(IC1-ROMCS)") (class "Default")
      (node (ref "IC1") (pin "13") (pinfunction "ROMCS_13") (pintype "output"))
      (node (ref "R28") (pin "1") (pinfunction "1_1") (pintype "passive"))
    )
    (net (code "85") (name "Net-(K2-P$1')") (class "Default")
      (node (ref "C11") (pin "1") (pinfunction "1_1") (pintype "passive"))
      (node (ref "C12") (pin "1") (pinfunction "1_1") (pintype "passive"))
      (node (ref "K2") (pin "1") (pinfunction "P$1_1") (pintype "bidirectional"))
      (node (ref "K2") (pin "1'") (pinfunction "P$1'_1'") (pintype "bidirectional"))
      (node (ref "R27") (pin "2") (pinfunction "2_2") (pintype "passive"))
    )
    (net (code "86") (name "Net-(K3-P$1')") (class "Default")
      (node (ref "C10") (pin "1") (pinfunction "1_1") (pintype "passive"))
      (node (ref "K3") (pin "1") (pinfunction "P$1_1") (pintype "bidirectional"))
      (node (ref "K3") (pin "1'") (pinfunction "P$1'_1'") (pintype "bidirectional"))
      (node (ref "R34") (pin "2") (pinfunction "2_2") (pintype "passive"))
    )
    (net (code "87") (name "Net-(KB2-1)") (class "Default")
      (node (ref "D1") (pin "A") (pinfunction "A_A") (pintype "passive"))
      (node (ref "KB2") (pin "P$1") (pinfunction "1_P$1") (pintype "bidirectional"))
    )
    (net (code "88") (name "Net-(KB2-2)") (class "Default")
      (node (ref "D2") (pin "A") (pinfunction "A_A") (pintype "passive"))
      (node (ref "KB2") (pin "P$2") (pinfunction "2_P$2") (pintype "bidirectional"))
    )
    (net (code "89") (name "Net-(KB2-3)") (class "Default")
      (node (ref "D3") (pin "A") (pinfunction "A_A") (pintype "passive"))
      (node (ref "KB2") (pin "P$3") (pinfunction "3_P$3") (pintype "bidirectional"))
    )
    (net (code "90") (name "Net-(KB2-4)") (class "Default")
      (node (ref "D4") (pin "A") (pinfunction "A_A") (pintype "passive"))
      (node (ref "KB2") (pin "P$4") (pinfunction "4_P$4") (pintype "bidirectional"))
    )
    (net (code "91") (name "Net-(KB2-5)") (class "Default")
      (node (ref "D5") (pin "A") (pinfunction "A_A") (pintype "passive"))
      (node (ref "KB2") (pin "P$5") (pinfunction "5_P$5") (pintype "bidirectional"))
    )
    (net (code "92") (name "Net-(KB2-6)") (class "Default")
      (node (ref "D6") (pin "A") (pinfunction "A_A") (pintype "passive"))
      (node (ref "KB2") (pin "P$6") (pinfunction "6_P$6") (pintype "bidirectional"))
    )
    (net (code "93") (name "Net-(KB2-7)") (class "Default")
      (node (ref "D7") (pin "A") (pinfunction "A_A") (pintype "passive"))
      (node (ref "KB2") (pin "P$7") (pinfunction "7_P$7") (pintype "bidirectional"))
    )
    (net (code "94") (name "Net-(KB2-8)") (class "Default")
      (node (ref "D8") (pin "A") (pinfunction "A_A") (pintype "passive"))
      (node (ref "KB2") (pin "P$8") (pinfunction "8_P$8") (pintype "bidirectional"))
    )
    (net (code "95") (name "Net-(R31-Pad2)") (class "Default")
      (node (ref "R31") (pin "2") (pinfunction "2_2") (pintype "passive"))
      (node (ref "R32") (pin "1") (pinfunction "1_1") (pintype "passive"))
    )
    (net (code "96") (name "Net-(T1-B)") (class "Default")
      (node (ref "C1") (pin "2") (pinfunction "2_2") (pintype "passive"))
      (node (ref "R1") (pin "2") (pinfunction "2_2") (pintype "passive"))
      (node (ref "T1") (pin "1") (pinfunction "B_1") (pintype "passive"))
    )
    (net (code "97") (name "Net-(T2-B)") (class "Default")
      (node (ref "C7") (pin "2") (pinfunction "2_2") (pintype "passive"))
      (node (ref "R3") (pin "2") (pinfunction "2_2") (pintype "passive"))
      (node (ref "R6") (pin "2") (pinfunction "2_2") (pintype "passive"))
      (node (ref "T2") (pin "1") (pinfunction "B_1") (pintype "passive"))
    )
    (net (code "98") (name "unconnected-(IC4-A10{slash}L-Pad21)") (class "Default")
      (node (ref "IC4") (pin "21") (pinfunction "A10/L_21") (pintype "output"))
    )
  )
)
